# RFID.net
KiCad netlist of a schematic drawn in EAGLE
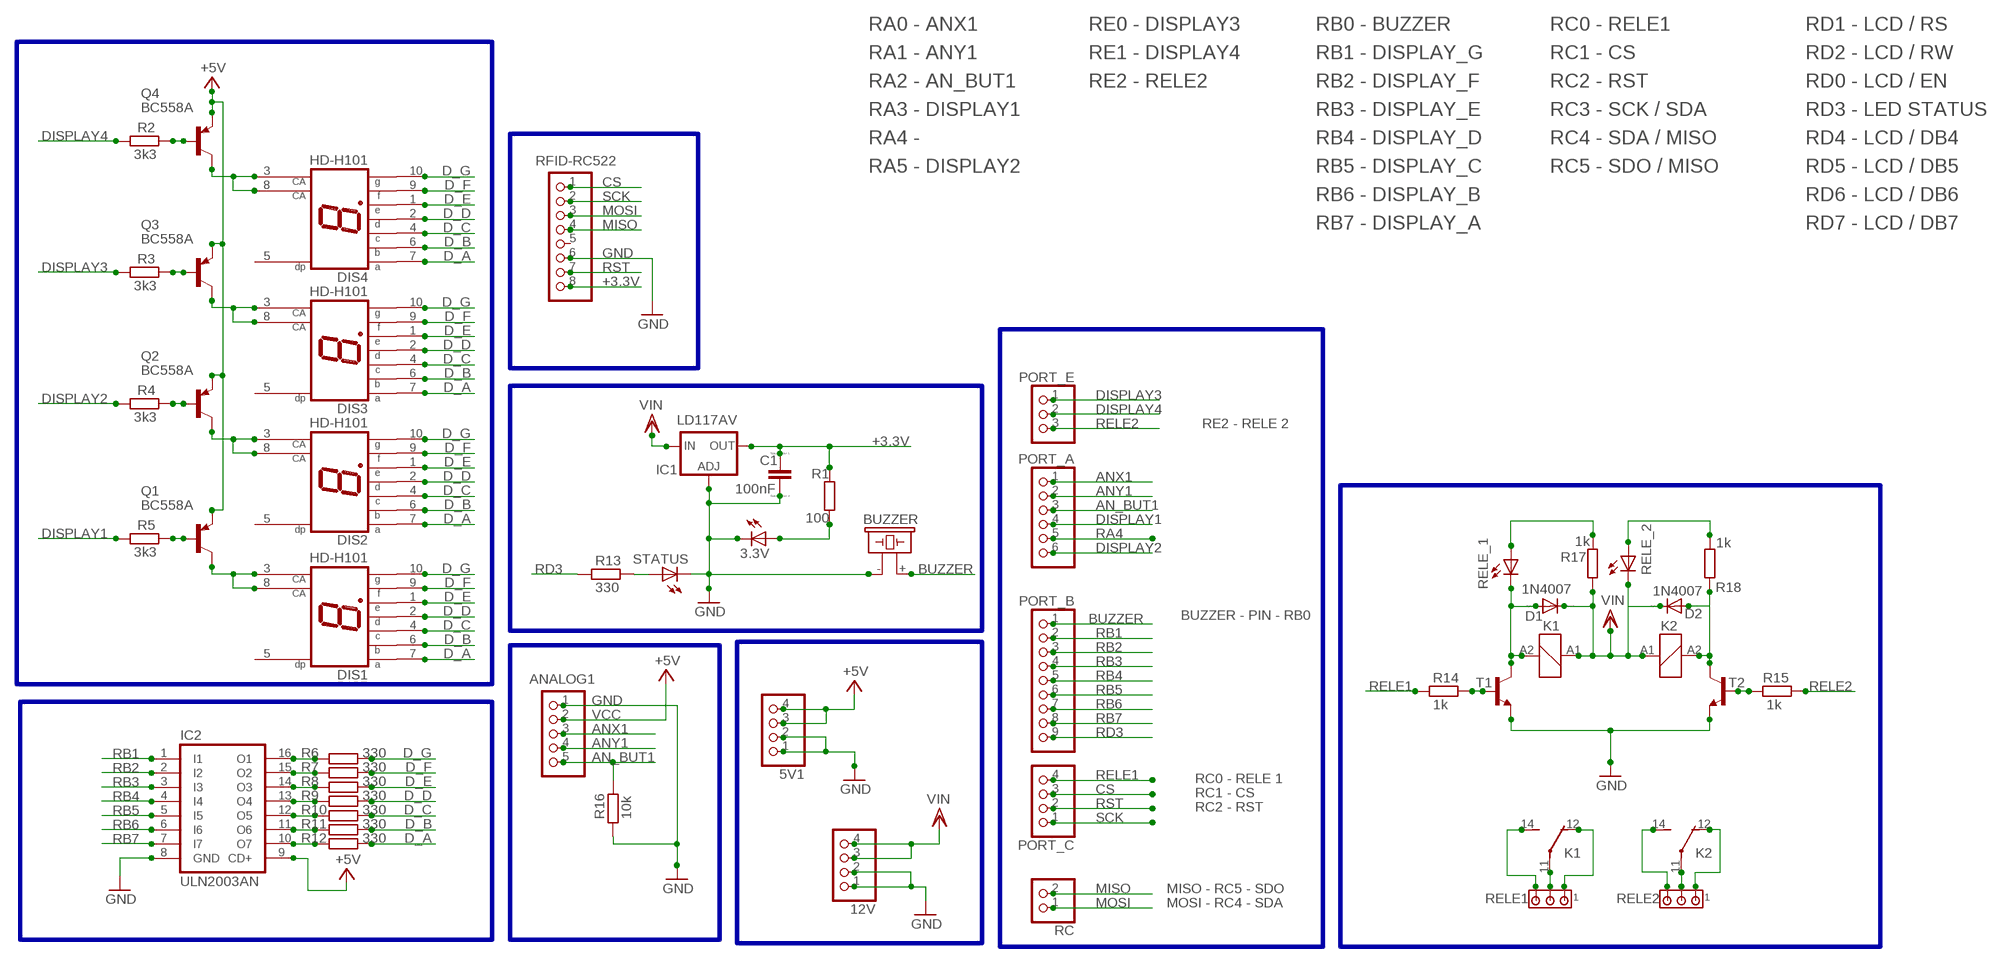
[diagram p0: schematic, sheet 1]

(export (version "E")
  (design (tool "Eeschema 10.0.6"))
  (components
    (comp (ref "3.3V")
      (value "LED5MM")
      (footprint "eagle-import:LED5MM")
      (libsource (lib "eagle-import") (part "LED5MM"))
    )
    (comp (ref "5V")
      (value "BUZZER")
      (footprint "eagle-import:F_CM12P")
      (libsource (lib "eagle-import") (part "F/CM12P"))
    )
    (comp (ref "5V1")
      (value "PINHD-1X4")
      (footprint "eagle-import:1X04")
      (libsource (lib "eagle-import") (part "PINHD-1X4"))
    )
    (comp (ref "12V")
      (value "PINHD-1X4")
      (footprint "eagle-import:1X04")
      (libsource (lib "eagle-import") (part "PINHD-1X4"))
    )
    (comp (ref "ANALOG1")
      (value "PINHD-1X5")
      (footprint "eagle-import:1X05")
      (libsource (lib "eagle-import") (part "PINHD-1X5"))
    )
    (comp (ref "C1")
      (value "100nF")
      (footprint "eagle-import:C050-025X075")
      (libsource (lib "eagle-import") (part "C-EU050-025X075"))
    )
    (comp (ref "D1")
      (value "1N4007")
      (footprint "eagle-import:DO41-10")
      (libsource (lib "eagle-import") (part "1N4004"))
    )
    (comp (ref "D2")
      (value "1N4007")
      (footprint "eagle-import:DO41-10")
      (libsource (lib "eagle-import") (part "1N4004"))
    )
    (comp (ref "DIS1")
      (value "HD-H101")
      (footprint "eagle-import:HDSP-M")
      (libsource (lib "eagle-import") (part "HD-H101"))
    )
    (comp (ref "DIS2")
      (value "HD-H101")
      (footprint "eagle-import:HDSP-M")
      (libsource (lib "eagle-import") (part "HD-H101"))
    )
    (comp (ref "DIS3")
      (value "HD-H101")
      (footprint "eagle-import:HDSP-M")
      (libsource (lib "eagle-import") (part "HD-H101"))
    )
    (comp (ref "DIS4")
      (value "HD-H101")
      (footprint "eagle-import:HDSP-M")
      (libsource (lib "eagle-import") (part "HD-H101"))
    )
    (comp (ref "IC1")
      (value "LD117AV")
      (footprint "eagle-import:TO220L1")
      (libsource (lib "eagle-import") (part "LD117A?V"))
    )
    (comp (ref "IC2")
      (value "ULN2003AN")
      (footprint "eagle-import:DIL16")
      (libsource (lib "eagle-import") (part "ULN2003AN"))
    )
    (comp (ref "JP1")
      (value "RFID-RC522")
      (footprint "eagle-import:1X08")
      (libsource (lib "eagle-import") (part "PINHD-1X8"))
    )
    (comp (ref "K1")
      (value "ZNS5106")
      (footprint "eagle-import:ZN5")
      (libsource (lib "eagle-import") (part "ZNS5106"))
    )
    (comp (ref "K2")
      (value "ZNS5106")
      (footprint "eagle-import:ZN5")
      (libsource (lib "eagle-import") (part "ZNS5106"))
    )
    (comp (ref "PORT_A")
      (value "PINHD-1X6")
      (footprint "eagle-import:1X06")
      (libsource (lib "eagle-import") (part "PINHD-1X6"))
    )
    (comp (ref "PORT_B")
      (value "PINHD-1X9")
      (footprint "eagle-import:1X09")
      (libsource (lib "eagle-import") (part "PINHD-1X9"))
    )
    (comp (ref "PORT_C")
      (value "PINHD-1X4")
      (footprint "eagle-import:1X04")
      (libsource (lib "eagle-import") (part "PINHD-1X4"))
    )
    (comp (ref "PORT_E")
      (value "PINHD-1X3")
      (footprint "eagle-import:1X03")
      (libsource (lib "eagle-import") (part "PINHD-1X3"))
    )
    (comp (ref "Q1")
      (value "BC558A")
      (footprint "eagle-import:TO92-EBC")
      (libsource (lib "eagle-import") (part "BC558A"))
    )
    (comp (ref "Q2")
      (value "BC558A")
      (footprint "eagle-import:TO92-EBC")
      (libsource (lib "eagle-import") (part "BC558A"))
    )
    (comp (ref "Q3")
      (value "BC558A")
      (footprint "eagle-import:TO92-EBC")
      (libsource (lib "eagle-import") (part "BC558A"))
    )
    (comp (ref "Q4")
      (value "BC558A")
      (footprint "eagle-import:TO92-EBC")
      (libsource (lib "eagle-import") (part "BC558A"))
    )
    (comp (ref "R1")
      (value "100")
      (footprint "eagle-import:0207_10")
      (libsource (lib "eagle-import") (part "R-EU_0207/10"))
    )
    (comp (ref "R2")
      (value "3k3")
      (footprint "eagle-import:0207_10")
      (libsource (lib "eagle-import") (part "R-EU_0207/10"))
    )
    (comp (ref "R3")
      (value "3k3")
      (footprint "eagle-import:0207_10")
      (libsource (lib "eagle-import") (part "R-EU_0207/10"))
    )
    (comp (ref "R4")
      (value "3k3")
      (footprint "eagle-import:0207_10")
      (libsource (lib "eagle-import") (part "R-EU_0207/10"))
    )
    (comp (ref "R5")
      (value "3k3")
      (footprint "eagle-import:0207_10")
      (libsource (lib "eagle-import") (part "R-EU_0207/10"))
    )
    (comp (ref "R6")
      (value "330")
      (footprint "eagle-import:0207_10")
      (libsource (lib "eagle-import") (part "R-EU_0207/10"))
    )
    (comp (ref "R7")
      (value "330")
      (footprint "eagle-import:0207_10")
      (libsource (lib "eagle-import") (part "R-EU_0207/10"))
    )
    (comp (ref "R8")
      (value "330")
      (footprint "eagle-import:0207_10")
      (libsource (lib "eagle-import") (part "R-EU_0207/10"))
    )
    (comp (ref "R9")
      (value "330")
      (footprint "eagle-import:0207_10")
      (libsource (lib "eagle-import") (part "R-EU_0207/10"))
    )
    (comp (ref "R10")
      (value "330")
      (footprint "eagle-import:0207_10")
      (libsource (lib "eagle-import") (part "R-EU_0207/10"))
    )
    (comp (ref "R11")
      (value "330")
      (footprint "eagle-import:0207_10")
      (libsource (lib "eagle-import") (part "R-EU_0207/10"))
    )
    (comp (ref "R12")
      (value "330")
      (footprint "eagle-import:0207_10")
      (libsource (lib "eagle-import") (part "R-EU_0207/10"))
    )
    (comp (ref "R13")
      (value "330")
      (footprint "eagle-import:0207_10")
      (libsource (lib "eagle-import") (part "R-EU_0207/10"))
    )
    (comp (ref "R14")
      (value "1k")
      (footprint "eagle-import:0207_10")
      (libsource (lib "eagle-import") (part "R-EU_0207/10"))
    )
    (comp (ref "R15")
      (value "1k")
      (footprint "eagle-import:0207_10")
      (libsource (lib "eagle-import") (part "R-EU_0207/10"))
    )
    (comp (ref "R16")
      (value "10k")
      (footprint "eagle-import:0207_10")
      (libsource (lib "eagle-import") (part "R-EU_0207/10"))
    )
    (comp (ref "R17")
      (value "1k")
      (footprint "eagle-import:0207_10")
      (libsource (lib "eagle-import") (part "R-EU_0207/10"))
    )
    (comp (ref "R18")
      (value "1k")
      (footprint "eagle-import:0207_10")
      (libsource (lib "eagle-import") (part "R-EU_0207/10"))
    )
    (comp (ref "RC")
      (value "PINHD-1X2")
      (footprint "eagle-import:1X02")
      (libsource (lib "eagle-import") (part "PINHD-1X2"))
    )
    (comp (ref "RELE1")
      (value "MTA03-156")
      (footprint "eagle-import:1X3MTA")
      (libsource (lib "eagle-import") (part "MTA03-156"))
    )
    (comp (ref "RELE2")
      (value "MTA03-156")
      (footprint "eagle-import:1X3MTA")
      (libsource (lib "eagle-import") (part "MTA03-156"))
    )
    (comp (ref "RELE_1")
      (value "LED5MM")
      (footprint "eagle-import:LED5MM")
      (libsource (lib "eagle-import") (part "LED5MM"))
    )
    (comp (ref "RELE_2")
      (value "LED5MM")
      (footprint "eagle-import:LED5MM")
      (libsource (lib "eagle-import") (part "LED5MM"))
    )
    (comp (ref "STATUS")
      (value "LED5MM")
      (footprint "eagle-import:LED5MM")
      (libsource (lib "eagle-import") (part "LED5MM"))
    )
    (comp (ref "T1")
      (value "BC548-NPN-TO92-CBE")
      (footprint "eagle-import:TO92-CBE")
      (libsource (lib "eagle-import") (part "-NPN-TO92-CBEBC548"))
    )
    (comp (ref "T2")
      (value "BC548-NPN-TO92-CBE")
      (footprint "eagle-import:TO92-CBE")
      (libsource (lib "eagle-import") (part "-NPN-TO92-CBEBC548"))
    )
  )
  (nets
    (net (code "1") (name "+5V") (class "Default")
      (node (ref "5V1") (pin "3") (pinfunction "3_3") (pintype "passive"))
      (node (ref "5V1") (pin "4") (pinfunction "4_4") (pintype "passive"))
      (node (ref "ANALOG1") (pin "2") (pinfunction "2_2") (pintype "passive"))
      (node (ref "IC2") (pin "9") (pinfunction "CD+_9") (pintype "passive"))
      (node (ref "Q1") (pin "E") (pinfunction "E_E") (pintype "passive"))
      (node (ref "Q2") (pin "E") (pinfunction "E_E") (pintype "passive"))
      (node (ref "Q3") (pin "E") (pinfunction "E_E") (pintype "passive"))
      (node (ref "Q4") (pin "E") (pinfunction "E_E") (pintype "passive"))
    )
    (net (code "2") (name "/+3.3V") (class "Default")
      (node (ref "C1") (pin "1") (pinfunction "1_1") (pintype "passive"))
      (node (ref "IC1") (pin "2") (pinfunction "OUT_2") (pintype "passive"))
      (node (ref "JP1") (pin "8") (pinfunction "8_8") (pintype "passive"))
      (node (ref "R1") (pin "2") (pinfunction "2_2") (pintype "passive"))
    )
    (net (code "3") (name "/ANX1") (class "Default")
      (node (ref "ANALOG1") (pin "3") (pinfunction "3_3") (pintype "passive"))
      (node (ref "PORT_A") (pin "1") (pinfunction "1_1") (pintype "passive"))
    )
    (net (code "4") (name "/ANY1") (class "Default")
      (node (ref "ANALOG1") (pin "4") (pinfunction "4_4") (pintype "passive"))
      (node (ref "PORT_A") (pin "2") (pinfunction "2_2") (pintype "passive"))
    )
    (net (code "5") (name "/AN_BUT1") (class "Default")
      (node (ref "ANALOG1") (pin "5") (pinfunction "5_5") (pintype "passive"))
      (node (ref "PORT_A") (pin "3") (pinfunction "3_3") (pintype "passive"))
      (node (ref "R16") (pin "1") (pinfunction "1_1") (pintype "passive"))
    )
    (net (code "6") (name "/BUZZER") (class "Default")
      (node (ref "5V") (pin "+") (pinfunction "1_+") (pintype "passive"))
      (node (ref "PORT_B") (pin "1") (pinfunction "1_1") (pintype "passive"))
    )
    (net (code "7") (name "/CS") (class "Default")
      (node (ref "JP1") (pin "1") (pinfunction "1_1") (pintype "passive"))
      (node (ref "PORT_C") (pin "3") (pinfunction "3_3") (pintype "passive"))
    )
    (net (code "8") (name "/DISPLAY1") (class "Default")
      (node (ref "PORT_A") (pin "4") (pinfunction "4_4") (pintype "passive"))
      (node (ref "R5") (pin "2") (pinfunction "2_2") (pintype "passive"))
    )
    (net (code "9") (name "/DISPLAY2") (class "Default")
      (node (ref "PORT_A") (pin "6") (pinfunction "6_6") (pintype "passive"))
      (node (ref "R4") (pin "2") (pinfunction "2_2") (pintype "passive"))
    )
    (net (code "10") (name "/DISPLAY3") (class "Default")
      (node (ref "PORT_E") (pin "1") (pinfunction "1_1") (pintype "passive"))
      (node (ref "R3") (pin "2") (pinfunction "2_2") (pintype "passive"))
    )
    (net (code "11") (name "/DISPLAY4") (class "Default")
      (node (ref "PORT_E") (pin "2") (pinfunction "2_2") (pintype "passive"))
      (node (ref "R2") (pin "2") (pinfunction "2_2") (pintype "passive"))
    )
    (net (code "12") (name "/D_A") (class "Default")
      (node (ref "DIS1") (pin "7") (pinfunction "A_7") (pintype "passive"))
      (node (ref "DIS2") (pin "7") (pinfunction "A_7") (pintype "passive"))
      (node (ref "DIS3") (pin "7") (pinfunction "A_7") (pintype "passive"))
      (node (ref "DIS4") (pin "7") (pinfunction "A_7") (pintype "passive"))
      (node (ref "R12") (pin "1") (pinfunction "1_1") (pintype "passive"))
    )
    (net (code "13") (name "/D_B") (class "Default")
      (node (ref "DIS1") (pin "6") (pinfunction "B_6") (pintype "passive"))
      (node (ref "DIS2") (pin "6") (pinfunction "B_6") (pintype "passive"))
      (node (ref "DIS3") (pin "6") (pinfunction "B_6") (pintype "passive"))
      (node (ref "DIS4") (pin "6") (pinfunction "B_6") (pintype "passive"))
      (node (ref "R11") (pin "1") (pinfunction "1_1") (pintype "passive"))
    )
    (net (code "14") (name "/D_C") (class "Default")
      (node (ref "DIS1") (pin "4") (pinfunction "C_4") (pintype "passive"))
      (node (ref "DIS2") (pin "4") (pinfunction "C_4") (pintype "passive"))
      (node (ref "DIS3") (pin "4") (pinfunction "C_4") (pintype "passive"))
      (node (ref "DIS4") (pin "4") (pinfunction "C_4") (pintype "passive"))
      (node (ref "R10") (pin "1") (pinfunction "1_1") (pintype "passive"))
    )
    (net (code "15") (name "/D_D") (class "Default")
      (node (ref "DIS1") (pin "2") (pinfunction "D_2") (pintype "passive"))
      (node (ref "DIS2") (pin "2") (pinfunction "D_2") (pintype "passive"))
      (node (ref "DIS3") (pin "2") (pinfunction "D_2") (pintype "passive"))
      (node (ref "DIS4") (pin "2") (pinfunction "D_2") (pintype "passive"))
      (node (ref "R9") (pin "1") (pinfunction "1_1") (pintype "passive"))
    )
    (net (code "16") (name "/D_E") (class "Default")
      (node (ref "DIS1") (pin "1") (pinfunction "E_1") (pintype "passive"))
      (node (ref "DIS2") (pin "1") (pinfunction "E_1") (pintype "passive"))
      (node (ref "DIS3") (pin "1") (pinfunction "E_1") (pintype "passive"))
      (node (ref "DIS4") (pin "1") (pinfunction "E_1") (pintype "passive"))
      (node (ref "R8") (pin "1") (pinfunction "1_1") (pintype "passive"))
    )
    (net (code "17") (name "/D_F") (class "Default")
      (node (ref "DIS1") (pin "9") (pinfunction "F_9") (pintype "passive"))
      (node (ref "DIS2") (pin "9") (pinfunction "F_9") (pintype "passive"))
      (node (ref "DIS3") (pin "9") (pinfunction "F_9") (pintype "passive"))
      (node (ref "DIS4") (pin "9") (pinfunction "F_9") (pintype "passive"))
      (node (ref "R7") (pin "1") (pinfunction "1_1") (pintype "passive"))
    )
    (net (code "18") (name "/D_G") (class "Default")
      (node (ref "DIS1") (pin "10") (pinfunction "G_10") (pintype "passive"))
      (node (ref "DIS2") (pin "10") (pinfunction "G_10") (pintype "passive"))
      (node (ref "DIS3") (pin "10") (pinfunction "G_10") (pintype "passive"))
      (node (ref "DIS4") (pin "10") (pinfunction "G_10") (pintype "passive"))
      (node (ref "R6") (pin "1") (pinfunction "1_1") (pintype "passive"))
    )
    (net (code "19") (name "/MISO") (class "Default")
      (node (ref "JP1") (pin "4") (pinfunction "4_4") (pintype "passive"))
      (node (ref "RC") (pin "2") (pinfunction "2_2") (pintype "passive"))
    )
    (net (code "20") (name "/MOSI") (class "Default")
      (node (ref "JP1") (pin "3") (pinfunction "3_3") (pintype "passive"))
      (node (ref "RC") (pin "1") (pinfunction "1_1") (pintype "passive"))
    )
    (net (code "21") (name "/RA4") (class "Default")
      (node (ref "PORT_A") (pin "5") (pinfunction "5_5") (pintype "passive"))
    )
    (net (code "22") (name "/RB1") (class "Default")
      (node (ref "IC2") (pin "1") (pinfunction "I1_1") (pintype "input"))
      (node (ref "PORT_B") (pin "2") (pinfunction "2_2") (pintype "passive"))
    )
    (net (code "23") (name "/RB2") (class "Default")
      (node (ref "IC2") (pin "2") (pinfunction "I2_2") (pintype "input"))
      (node (ref "PORT_B") (pin "3") (pinfunction "3_3") (pintype "passive"))
    )
    (net (code "24") (name "/RB3") (class "Default")
      (node (ref "IC2") (pin "3") (pinfunction "I3_3") (pintype "input"))
      (node (ref "PORT_B") (pin "4") (pinfunction "4_4") (pintype "passive"))
    )
    (net (code "25") (name "/RB4") (class "Default")
      (node (ref "IC2") (pin "4") (pinfunction "I4_4") (pintype "input"))
      (node (ref "PORT_B") (pin "5") (pinfunction "5_5") (pintype "passive"))
    )
    (net (code "26") (name "/RB5") (class "Default")
      (node (ref "IC2") (pin "5") (pinfunction "I5_5") (pintype "input"))
      (node (ref "PORT_B") (pin "6") (pinfunction "6_6") (pintype "passive"))
    )
    (net (code "27") (name "/RB6") (class "Default")
      (node (ref "IC2") (pin "6") (pinfunction "I6_6") (pintype "input"))
      (node (ref "PORT_B") (pin "7") (pinfunction "7_7") (pintype "passive"))
    )
    (net (code "28") (name "/RB7") (class "Default")
      (node (ref "IC2") (pin "7") (pinfunction "I7_7") (pintype "input"))
      (node (ref "PORT_B") (pin "8") (pinfunction "8_8") (pintype "passive"))
    )
    (net (code "29") (name "/RD3") (class "Default")
      (node (ref "PORT_B") (pin "9") (pinfunction "9_9") (pintype "passive"))
      (node (ref "R13") (pin "2") (pinfunction "2_2") (pintype "passive"))
    )
    (net (code "30") (name "/RELE1") (class "Default")
      (node (ref "PORT_C") (pin "4") (pinfunction "4_4") (pintype "passive"))
      (node (ref "R14") (pin "2") (pinfunction "2_2") (pintype "passive"))
    )
    (net (code "31") (name "/RELE2") (class "Default")
      (node (ref "PORT_E") (pin "3") (pinfunction "3_3") (pintype "passive"))
      (node (ref "R15") (pin "1") (pinfunction "1_1") (pintype "passive"))
    )
    (net (code "32") (name "/RST") (class "Default")
      (node (ref "JP1") (pin "7") (pinfunction "7_7") (pintype "passive"))
      (node (ref "PORT_C") (pin "2") (pinfunction "2_2") (pintype "passive"))
    )
    (net (code "33") (name "/SCK") (class "Default")
      (node (ref "JP1") (pin "2") (pinfunction "2_2") (pintype "passive"))
      (node (ref "PORT_C") (pin "1") (pinfunction "1_1") (pintype "passive"))
    )
    (net (code "34") (name "GND") (class "Default")
      (node (ref "12V") (pin "1") (pinfunction "1_1") (pintype "passive"))
      (node (ref "12V") (pin "2") (pinfunction "2_2") (pintype "passive"))
      (node (ref "3.3V") (pin "K") (pinfunction "C_K") (pintype "passive"))
      (node (ref "5V") (pin "-") (pinfunction "2_-") (pintype "passive"))
      (node (ref "5V1") (pin "1") (pinfunction "1_1") (pintype "passive"))
      (node (ref "5V1") (pin "2") (pinfunction "2_2") (pintype "passive"))
      (node (ref "ANALOG1") (pin "1") (pinfunction "1_1") (pintype "passive"))
      (node (ref "C1") (pin "2") (pinfunction "2_2") (pintype "passive"))
      (node (ref "IC1") (pin "1") (pinfunction "ADJ_1") (pintype "input"))
      (node (ref "IC2") (pin "8") (pinfunction "GND_8") (pintype "power_in"))
      (node (ref "JP1") (pin "6") (pinfunction "6_6") (pintype "passive"))
      (node (ref "R16") (pin "2") (pinfunction "2_2") (pintype "passive"))
      (node (ref "STATUS") (pin "K") (pinfunction "C_K") (pintype "passive"))
      (node (ref "T1") (pin "E") (pinfunction "E_E") (pintype "passive"))
      (node (ref "T2") (pin "E") (pinfunction "E_E") (pintype "passive"))
    )
    (net (code "35") (name "Net-(3.3V-PadA)") (class "Default")
      (node (ref "3.3V") (pin "A") (pinfunction "A_A") (pintype "passive"))
      (node (ref "R1") (pin "1") (pinfunction "1_1") (pintype "passive"))
    )
    (net (code "36") (name "Net-(DIS1-CA-Pad3)") (class "Default")
      (node (ref "DIS1") (pin "3") (pinfunction "CA_3") (pintype "passive"))
      (node (ref "DIS1") (pin "8") (pinfunction "CA_8") (pintype "passive"))
      (node (ref "Q1") (pin "C") (pinfunction "C_C") (pintype "passive"))
    )
    (net (code "37") (name "Net-(DIS2-CA-Pad3)") (class "Default")
      (node (ref "DIS2") (pin "3") (pinfunction "CA_3") (pintype "passive"))
      (node (ref "DIS2") (pin "8") (pinfunction "CA_8") (pintype "passive"))
      (node (ref "Q2") (pin "C") (pinfunction "C_C") (pintype "passive"))
    )
    (net (code "38") (name "Net-(DIS3-CA-Pad3)") (class "Default")
      (node (ref "DIS3") (pin "3") (pinfunction "CA_3") (pintype "passive"))
      (node (ref "DIS3") (pin "8") (pinfunction "CA_8") (pintype "passive"))
      (node (ref "Q3") (pin "C") (pinfunction "C_C") (pintype "passive"))
    )
    (net (code "39") (name "Net-(DIS4-CA-Pad3)") (class "Default")
      (node (ref "DIS4") (pin "3") (pinfunction "CA_3") (pintype "passive"))
      (node (ref "DIS4") (pin "8") (pinfunction "CA_8") (pintype "passive"))
      (node (ref "Q4") (pin "C") (pinfunction "C_C") (pintype "passive"))
    )
    (net (code "40") (name "Net-(IC2-O1)") (class "Default")
      (node (ref "IC2") (pin "16") (pinfunction "O1_16") (pintype "open_collector"))
      (node (ref "R6") (pin "2") (pinfunction "2_2") (pintype "passive"))
    )
    (net (code "41") (name "Net-(IC2-O2)") (class "Default")
      (node (ref "IC2") (pin "15") (pinfunction "O2_15") (pintype "open_collector"))
      (node (ref "R7") (pin "2") (pinfunction "2_2") (pintype "passive"))
    )
    (net (code "42") (name "Net-(IC2-O3)") (class "Default")
      (node (ref "IC2") (pin "14") (pinfunction "O3_14") (pintype "open_collector"))
      (node (ref "R8") (pin "2") (pinfunction "2_2") (pintype "passive"))
    )
    (net (code "43") (name "Net-(IC2-O4)") (class "Default")
      (node (ref "IC2") (pin "13") (pinfunction "O4_13") (pintype "open_collector"))
      (node (ref "R9") (pin "2") (pinfunction "2_2") (pintype "passive"))
    )
    (net (code "44") (name "Net-(IC2-O5)") (class "Default")
      (node (ref "IC2") (pin "12") (pinfunction "O5_12") (pintype "open_collector"))
      (node (ref "R10") (pin "2") (pinfunction "2_2") (pintype "passive"))
    )
    (net (code "45") (name "Net-(IC2-O6)") (class "Default")
      (node (ref "IC2") (pin "11") (pinfunction "O6_11") (pintype "open_collector"))
      (node (ref "R11") (pin "2") (pinfunction "2_2") (pintype "passive"))
    )
    (net (code "46") (name "Net-(IC2-O7)") (class "Default")
      (node (ref "IC2") (pin "10") (pinfunction "O7_10") (pintype "open_collector"))
      (node (ref "R12") (pin "2") (pinfunction "2_2") (pintype "passive"))
    )
    (net (code "47") (name "Net-(K1A-2)") (class "Default")
      (node (ref "D1") (pin "A") (pinfunction "A_A") (pintype "passive"))
      (node (ref "K1") (pin "A2") (pinfunction "2_A2") (pintype "passive"))
      (node (ref "RELE_1") (pin "K") (pinfunction "C_K") (pintype "passive"))
      (node (ref "T1") (pin "C") (pinfunction "C_C") (pintype "passive"))
    )
    (net (code "48") (name "Net-(K1B-O)") (class "Default")
      (node (ref "K1") (pin "12") (pinfunction "O_12") (pintype "passive"))
      (node (ref "RELE1") (pin "1") (pinfunction "1_1") (pintype "passive"))
    )
    (net (code "49") (name "Net-(K1B-P)") (class "Default")
      (node (ref "K1") (pin "11") (pinfunction "P_11") (pintype "passive"))
      (node (ref "RELE1") (pin "2") (pinfunction "2_2") (pintype "passive"))
    )
    (net (code "50") (name "Net-(K1B-S)") (class "Default")
      (node (ref "K1") (pin "14") (pinfunction "S_14") (pintype "passive"))
      (node (ref "RELE1") (pin "3") (pinfunction "3_3") (pintype "passive"))
    )
    (net (code "51") (name "Net-(K2A-2)") (class "Default")
      (node (ref "D2") (pin "A") (pinfunction "A_A") (pintype "passive"))
      (node (ref "K2") (pin "A2") (pinfunction "2_A2") (pintype "passive"))
      (node (ref "R18") (pin "2") (pinfunction "2_2") (pintype "passive"))
      (node (ref "T2") (pin "C") (pinfunction "C_C") (pintype "passive"))
    )
    (net (code "52") (name "Net-(K2B-O)") (class "Default")
      (node (ref "K2") (pin "12") (pinfunction "O_12") (pintype "passive"))
      (node (ref "RELE2") (pin "1") (pinfunction "1_1") (pintype "passive"))
    )
    (net (code "53") (name "Net-(K2B-P)") (class "Default")
      (node (ref "K2") (pin "11") (pinfunction "P_11") (pintype "passive"))
      (node (ref "RELE2") (pin "2") (pinfunction "2_2") (pintype "passive"))
    )
    (net (code "54") (name "Net-(K2B-S)") (class "Default")
      (node (ref "K2") (pin "14") (pinfunction "S_14") (pintype "passive"))
      (node (ref "RELE2") (pin "3") (pinfunction "3_3") (pintype "passive"))
    )
    (net (code "55") (name "Net-(Q1-PadB)") (class "Default")
      (node (ref "Q1") (pin "B") (pinfunction "B_B") (pintype "passive"))
      (node (ref "R5") (pin "1") (pinfunction "1_1") (pintype "passive"))
    )
    (net (code "56") (name "Net-(Q2-PadB)") (class "Default")
      (node (ref "Q2") (pin "B") (pinfunction "B_B") (pintype "passive"))
      (node (ref "R4") (pin "1") (pinfunction "1_1") (pintype "passive"))
    )
    (net (code "57") (name "Net-(Q3-PadB)") (class "Default")
      (node (ref "Q3") (pin "B") (pinfunction "B_B") (pintype "passive"))
      (node (ref "R3") (pin "1") (pinfunction "1_1") (pintype "passive"))
    )
    (net (code "58") (name "Net-(Q4-PadB)") (class "Default")
      (node (ref "Q4") (pin "B") (pinfunction "B_B") (pintype "passive"))
      (node (ref "R2") (pin "1") (pinfunction "1_1") (pintype "passive"))
    )
    (net (code "59") (name "Net-(R13-Pad1)") (class "Default")
      (node (ref "R13") (pin "1") (pinfunction "1_1") (pintype "passive"))
      (node (ref "STATUS") (pin "A") (pinfunction "A_A") (pintype "passive"))
    )
    (net (code "60") (name "Net-(R14-Pad1)") (class "Default")
      (node (ref "R14") (pin "1") (pinfunction "1_1") (pintype "passive"))
      (node (ref "T1") (pin "B") (pinfunction "B_B") (pintype "passive"))
    )
    (net (code "61") (name "Net-(R15-Pad2)") (class "Default")
      (node (ref "R15") (pin "2") (pinfunction "2_2") (pintype "passive"))
      (node (ref "T2") (pin "B") (pinfunction "B_B") (pintype "passive"))
    )
    (net (code "62") (name "Net-(R17-Pad2)") (class "Default")
      (node (ref "R17") (pin "2") (pinfunction "2_2") (pintype "passive"))
      (node (ref "RELE_1") (pin "A") (pinfunction "A_A") (pintype "passive"))
    )
    (net (code "63") (name "Net-(R18-Pad1)") (class "Default")
      (node (ref "R18") (pin "1") (pinfunction "1_1") (pintype "passive"))
      (node (ref "RELE_2") (pin "A") (pinfunction "A_A") (pintype "passive"))
    )
    (net (code "64") (name "VIN") (class "Default")
      (node (ref "12V") (pin "3") (pinfunction "3_3") (pintype "passive"))
      (node (ref "12V") (pin "4") (pinfunction "4_4") (pintype "passive"))
      (node (ref "D1") (pin "C") (pinfunction "C_C") (pintype "passive"))
      (node (ref "D2") (pin "C") (pinfunction "C_C") (pintype "passive"))
      (node (ref "IC1") (pin "3") (pinfunction "IN_3") (pintype "input"))
      (node (ref "K1") (pin "A1") (pinfunction "1_A1") (pintype "passive"))
      (node (ref "K2") (pin "A1") (pinfunction "1_A1") (pintype "passive"))
      (node (ref "R17") (pin "1") (pinfunction "1_1") (pintype "passive"))
      (node (ref "RELE_2") (pin "K") (pinfunction "C_K") (pintype "passive"))
    )
    (net (code "65") (name "unconnected-(DIS1-DP-Pad5)") (class "Default")
      (node (ref "DIS1") (pin "5") (pinfunction "DP_5") (pintype "passive"))
    )
    (net (code "66") (name "unconnected-(DIS2-DP-Pad5)") (class "Default")
      (node (ref "DIS2") (pin "5") (pinfunction "DP_5") (pintype "passive"))
    )
    (net (code "67") (name "unconnected-(DIS3-DP-Pad5)") (class "Default")
      (node (ref "DIS3") (pin "5") (pinfunction "DP_5") (pintype "passive"))
    )
    (net (code "68") (name "unconnected-(DIS4-DP-Pad5)") (class "Default")
      (node (ref "DIS4") (pin "5") (pinfunction "DP_5") (pintype "passive"))
    )
    (net (code "69") (name "unconnected-(JP1-Pad5)") (class "Default")
      (node (ref "JP1") (pin "5") (pinfunction "5_5") (pintype "passive"))
    )
  )
)
